# SCH_CameraTrap_2022-12-09.net
KiCad netlist of a schematic drawn in EasyEDA
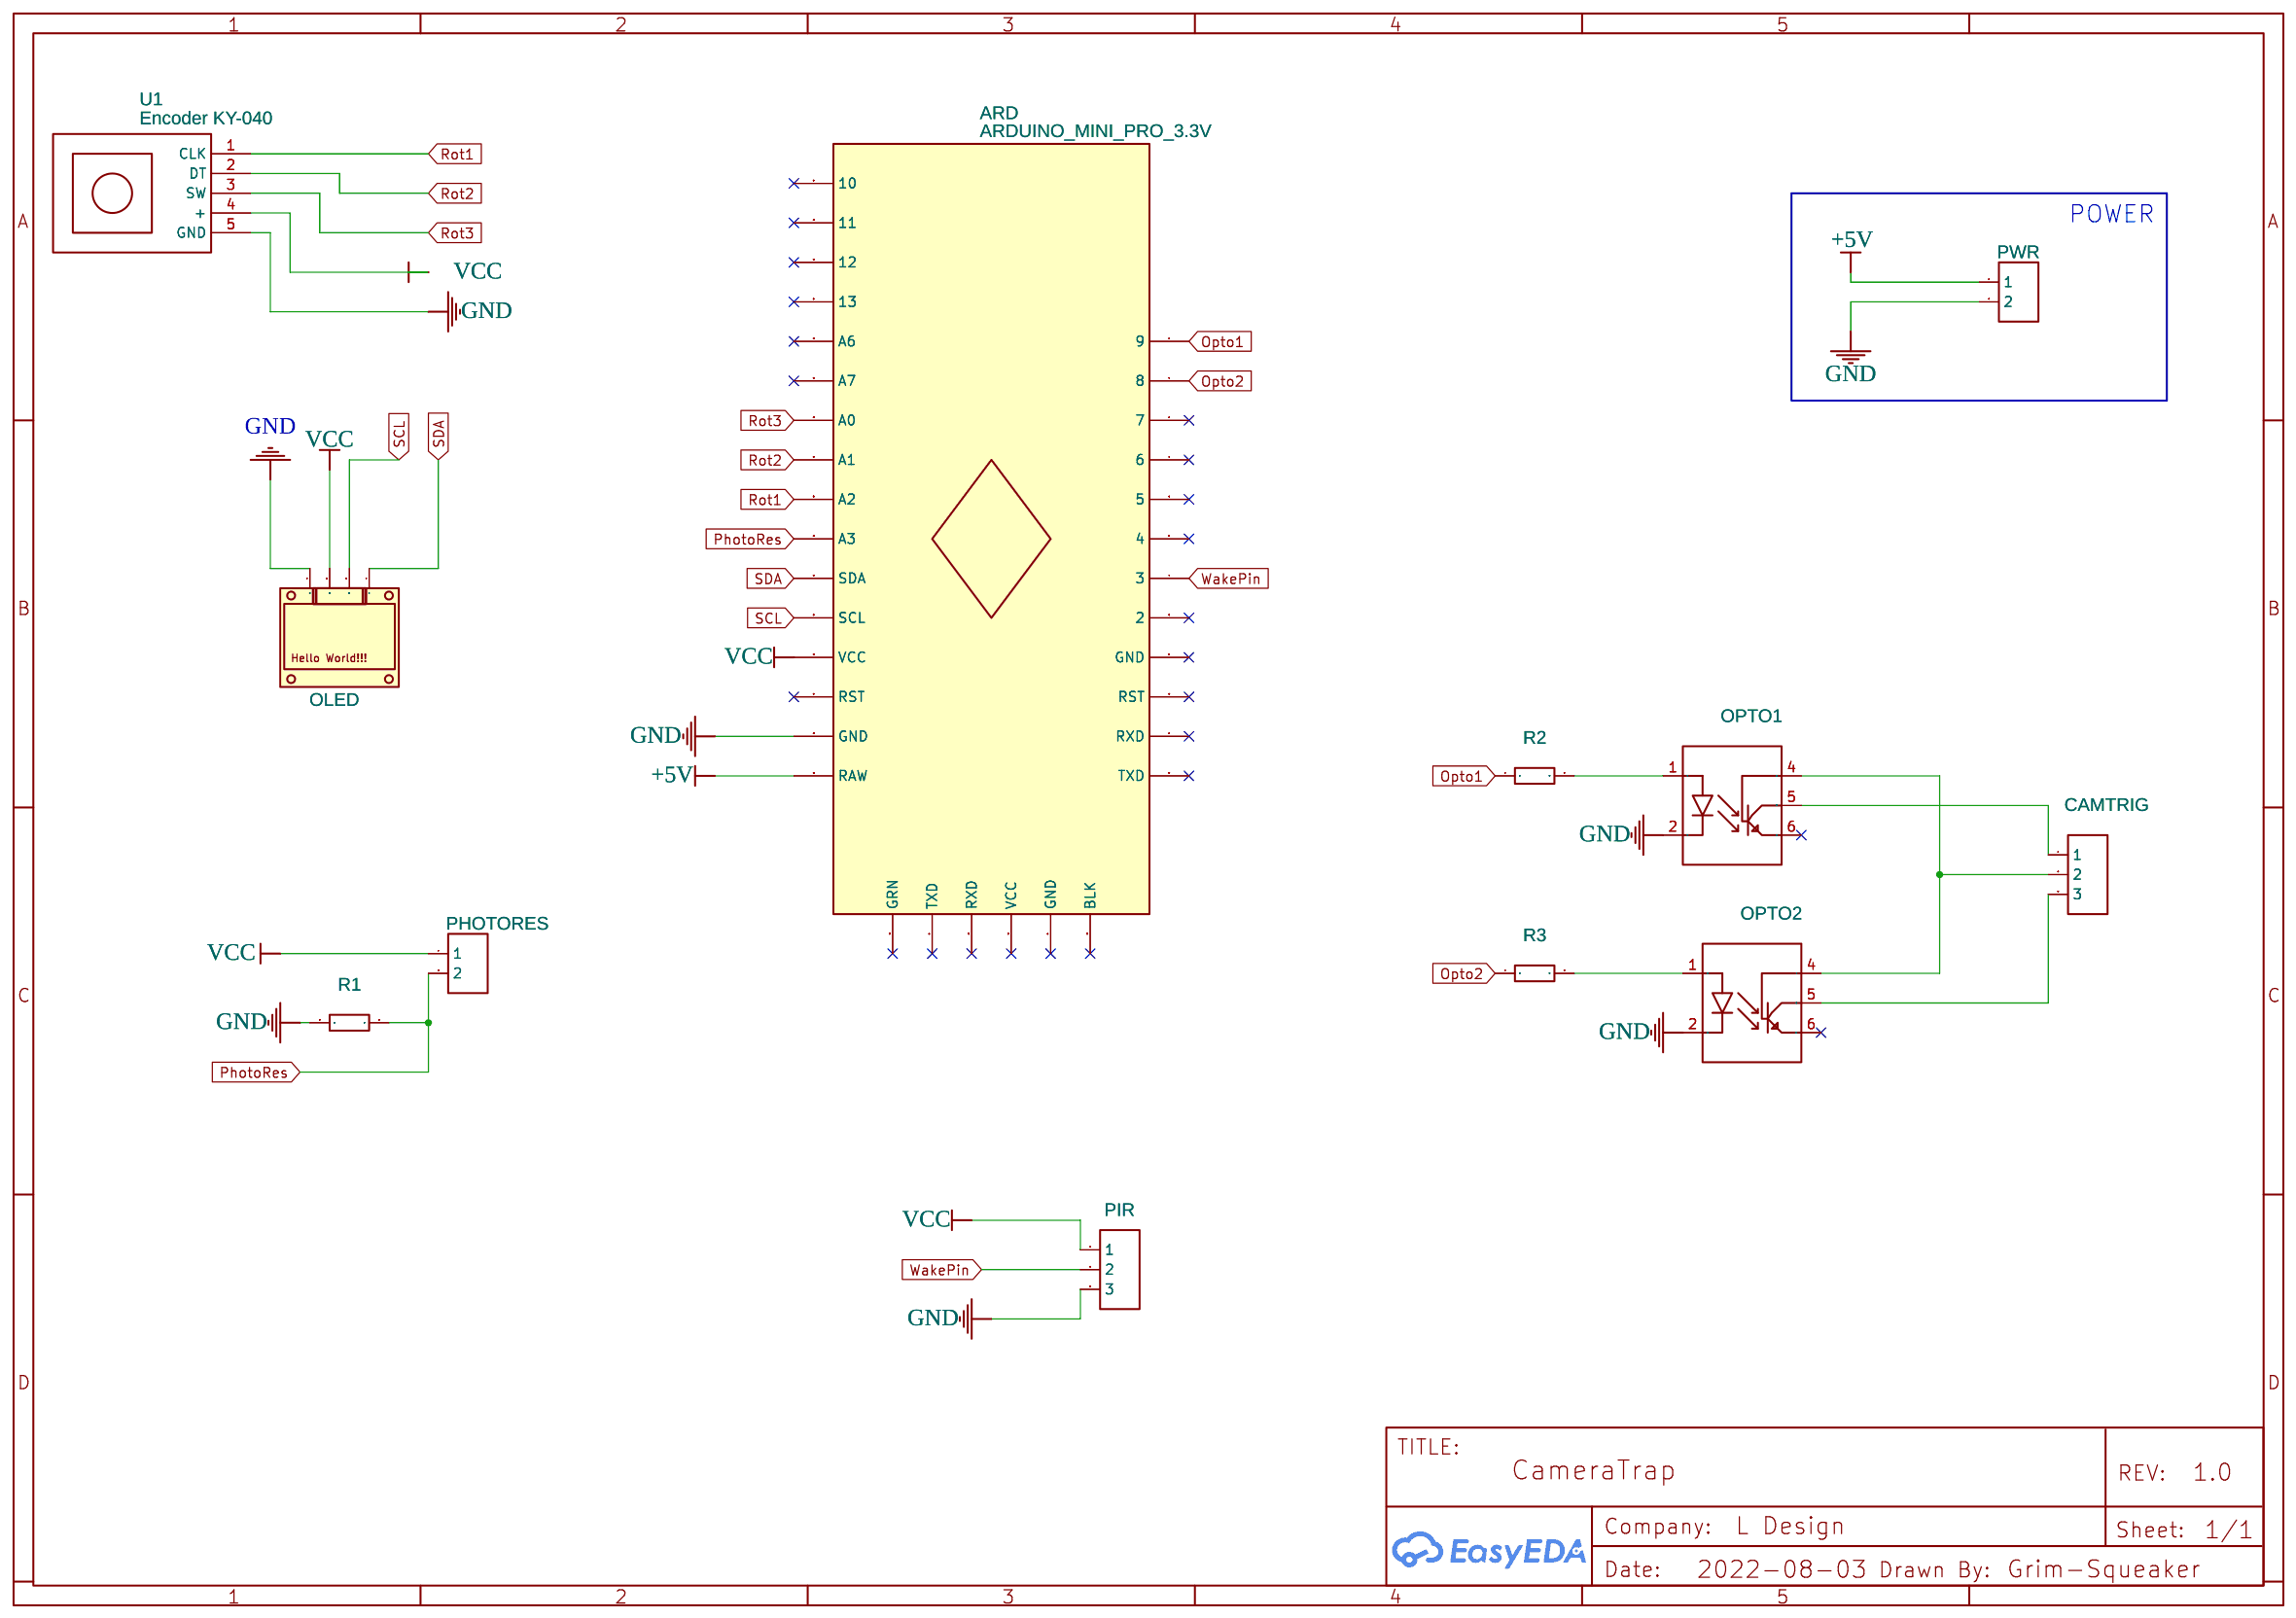
[diagram p0: schematic sheet]

(export (version "E")
  (design (tool "Eeschema 10.0.6"))
  (components
    (comp (ref "ARD")
      (value "ARDUINO_MINI_PRO_3.3V")
      (fields (field (name "BOM_Manufacturer Part") "Spurkfun"))
      (libsource (lib "") (part "ARDUINO_MINI_PRO_3.3V"))
    )
    (comp (ref "CAMTRIG")
      (value "HDR-F-2.54_1x3")
      (fields (field (name "BOM_Supplier Part") "C146690"))
      (libsource (lib "") (part "HDR-F-2.54_1x3_1"))
    )
    (comp (ref "OLED1") (value "OLED") (libsource (lib "") (part "0.96OLED_4P")))
    (comp (ref "OPTO1") (value "CNY-17") (libsource (lib "") (part "CNY-17")))
    (comp (ref "OPTO2") (value "CNY-17") (libsource (lib "") (part "CNY-17")))
    (comp (ref "PHOTORES")
      (value "HDR-F-2.54_1x2")
      (fields (field (name "BOM_Supplier Part") "C49661"))
      (libsource (lib "") (part "HDR-F-2.54_1x2_1"))
    )
    (comp (ref "PIR")
      (value "HDR-F-2.54_1x3")
      (fields (field (name "BOM_Supplier Part") "C146690"))
      (libsource (lib "") (part "HDR-F-2.54_1x3"))
    )
    (comp (ref "PWR")
      (value "HDR-F-2.54_1x2")
      (fields (field (name "BOM_Supplier Part") "C49661"))
      (libsource (lib "") (part "HDR-F-2.54_1x2"))
    )
    (comp (ref "R1")
      (value "10K")
      (fields
        (field (name "BOM_Manufacturer Part") "EWWR0006J10K0T9")
        (field (name "BOM_Supplier Part") "C348946")
      )
      (libsource (lib "") (part "Resistor TH"))
    )
    (comp (ref "R2")
      (value "10K")
      (fields
        (field (name "BOM_Manufacturer Part") "EWWR0006J10K0T9")
        (field (name "BOM_Supplier Part") "C348946")
      )
      (libsource (lib "") (part "Resistor TH"))
    )
    (comp (ref "R3")
      (value "10K")
      (fields
        (field (name "BOM_Manufacturer Part") "EWWR0006J10K0T9")
        (field (name "BOM_Supplier Part") "C348946")
      )
      (libsource (lib "") (part "Resistor TH"))
    )
    (comp (ref "U1") (value "Encoder KY-040") (libsource (lib "") (part "Encoder KY-040")))
  )
  (nets
    (net (code "1") (name "+5V") (class "Default")
      (node (ref "ARD") (pin "19") (pinfunction "RAW_19") (pintype "unspecified"))
      (node (ref "PWR") (pin "1") (pinfunction "1_1") (pintype "input"))
    )
    (net (code "2") (name "GND") (class "Default")
      (node (ref "ARD") (pin "20") (pinfunction "GND_20") (pintype "unspecified"))
      (node (ref "OLED1") (pin "1") (pinfunction "1_1") (pintype "unspecified"))
      (node (ref "OPTO1") (pin "2") (pinfunction "2_2") (pintype "unspecified"))
      (node (ref "OPTO2") (pin "2") (pinfunction "2_2") (pintype "unspecified"))
      (node (ref "PIR") (pin "3") (pinfunction "3_3") (pintype "input"))
      (node (ref "PWR") (pin "2") (pinfunction "2_2") (pintype "input"))
      (node (ref "R1") (pin "1") (pinfunction "1_1") (pintype "unspecified"))
      (node (ref "U1") (pin "5") (pinfunction "GND_5") (pintype "unspecified"))
    )
    (net (code "3") (name "Net-(CAMTRIG-Pad1)") (class "Default")
      (node (ref "CAMTRIG") (pin "1") (pinfunction "1_1") (pintype "input"))
      (node (ref "OPTO1") (pin "5") (pinfunction "5_5") (pintype "unspecified"))
    )
    (net (code "4") (name "Net-(CAMTRIG-Pad2)") (class "Default")
      (node (ref "CAMTRIG") (pin "2") (pinfunction "2_2") (pintype "input"))
      (node (ref "OPTO1") (pin "4") (pinfunction "4_4") (pintype "unspecified"))
      (node (ref "OPTO2") (pin "4") (pinfunction "4_4") (pintype "unspecified"))
    )
    (net (code "5") (name "Net-(CAMTRIG-Pad3)") (class "Default")
      (node (ref "CAMTRIG") (pin "3") (pinfunction "3_3") (pintype "input"))
      (node (ref "OPTO2") (pin "5") (pinfunction "5_5") (pintype "unspecified"))
    )
    (net (code "6") (name "Net-(OPTO1-Pad1)") (class "Default")
      (node (ref "OPTO1") (pin "1") (pinfunction "1_1") (pintype "unspecified"))
      (node (ref "R2") (pin "2") (pinfunction "2_2") (pintype "unspecified"))
    )
    (net (code "7") (name "Net-(OPTO2-Pad1)") (class "Default")
      (node (ref "OPTO2") (pin "1") (pinfunction "1_1") (pintype "unspecified"))
      (node (ref "R3") (pin "2") (pinfunction "2_2") (pintype "unspecified"))
    )
    (net (code "8") (name "Opto1") (class "Default")
      (node (ref "ARD") (pin "1") (pinfunction "9_1") (pintype "unspecified"))
      (node (ref "R2") (pin "1") (pinfunction "1_1") (pintype "unspecified"))
    )
    (net (code "9") (name "Opto2") (class "Default")
      (node (ref "ARD") (pin "2") (pinfunction "8_2") (pintype "unspecified"))
      (node (ref "R3") (pin "1") (pinfunction "1_1") (pintype "unspecified"))
    )
    (net (code "10") (name "PhotoRes") (class "Default")
      (node (ref "ARD") (pin "25") (pinfunction "A3_25") (pintype "unspecified"))
      (node (ref "PHOTORES") (pin "2") (pinfunction "2_2") (pintype "input"))
      (node (ref "R1") (pin "2") (pinfunction "2_2") (pintype "unspecified"))
    )
    (net (code "11") (name "Rot1") (class "Default")
      (node (ref "ARD") (pin "26") (pinfunction "A2_26") (pintype "unspecified"))
      (node (ref "U1") (pin "1") (pinfunction "CLK_1") (pintype "unspecified"))
    )
    (net (code "12") (name "Rot2") (class "Default")
      (node (ref "ARD") (pin "27") (pinfunction "A1_27") (pintype "unspecified"))
      (node (ref "U1") (pin "2") (pinfunction "DT_2") (pintype "unspecified"))
    )
    (net (code "13") (name "Rot3") (class "Default")
      (node (ref "ARD") (pin "28") (pinfunction "A0_28") (pintype "unspecified"))
      (node (ref "U1") (pin "3") (pinfunction "SW_3") (pintype "unspecified"))
    )
    (net (code "14") (name "SCL") (class "Default")
      (node (ref "ARD") (pin "23") (pinfunction "SCL_23") (pintype "unspecified"))
      (node (ref "OLED1") (pin "3") (pinfunction "3_3") (pintype "unspecified"))
    )
    (net (code "15") (name "SDA") (class "Default")
      (node (ref "ARD") (pin "24") (pinfunction "SDA_24") (pintype "unspecified"))
      (node (ref "OLED1") (pin "4") (pinfunction "4_4") (pintype "unspecified"))
    )
    (net (code "16") (name "VCC") (class "Default")
      (node (ref "ARD") (pin "22") (pinfunction "VCC_22") (pintype "unspecified"))
      (node (ref "OLED1") (pin "2") (pinfunction "2_2") (pintype "unspecified"))
      (node (ref "PHOTORES") (pin "1") (pinfunction "1_1") (pintype "input"))
      (node (ref "PIR") (pin "1") (pinfunction "1_1") (pintype "input"))
      (node (ref "U1") (pin "4") (pinfunction "+_4") (pintype "unspecified"))
    )
    (net (code "17") (name "WakePin") (class "Default")
      (node (ref "ARD") (pin "7") (pinfunction "3_7") (pintype "unspecified"))
      (node (ref "PIR") (pin "2") (pinfunction "2_2") (pintype "input"))
    )
    (net (code "18") (name "unconnected-(ARD-2-Pad8)") (class "Default")
      (node (ref "ARD") (pin "8") (pinfunction "2_8") (pintype "unspecified+no_connect"))
    )
    (net (code "19") (name "unconnected-(ARD-4-Pad6)") (class "Default")
      (node (ref "ARD") (pin "6") (pinfunction "4_6") (pintype "unspecified+no_connect"))
    )
    (net (code "20") (name "unconnected-(ARD-6-Pad4)") (class "Default")
      (node (ref "ARD") (pin "4") (pinfunction "6_4") (pintype "unspecified+no_connect"))
    )
    (net (code "21") (name "unconnected-(ARD-7-Pad3)") (class "Default")
      (node (ref "ARD") (pin "3") (pinfunction "7_3") (pintype "unspecified+no_connect"))
    )
    (net (code "22") (name "unconnected-(ARD-10-Pad34)") (class "Default")
      (node (ref "ARD") (pin "34") (pinfunction "10_34") (pintype "unspecified+no_connect"))
    )
    (net (code "23") (name "unconnected-(ARD-11-Pad33)") (class "Default")
      (node (ref "ARD") (pin "33") (pinfunction "11_33") (pintype "unspecified+no_connect"))
    )
    (net (code "24") (name "unconnected-(ARD-12-Pad32)") (class "Default")
      (node (ref "ARD") (pin "32") (pinfunction "12_32") (pintype "unspecified+no_connect"))
    )
    (net (code "25") (name "unconnected-(ARD-13-Pad31)") (class "Default")
      (node (ref "ARD") (pin "31") (pinfunction "13_31") (pintype "unspecified+no_connect"))
    )
    (net (code "26") (name "unconnected-(ARD-A6-Pad30)") (class "Default")
      (node (ref "ARD") (pin "30") (pinfunction "A6_30") (pintype "unspecified+no_connect"))
    )
    (net (code "27") (name "unconnected-(ARD-A7-Pad29)") (class "Default")
      (node (ref "ARD") (pin "29") (pinfunction "A7_29") (pintype "unspecified+no_connect"))
    )
    (net (code "28") (name "unconnected-(ARD-BLK-Pad13)") (class "Default")
      (node (ref "ARD") (pin "13") (pinfunction "BLK_13") (pintype "unspecified+no_connect"))
    )
    (net (code "29") (name "unconnected-(ARD-GND-Pad9)") (class "Default")
      (node (ref "ARD") (pin "9") (pinfunction "GND_9") (pintype "unspecified+no_connect"))
    )
    (net (code "30") (name "unconnected-(ARD-GND-Pad14)") (class "Default")
      (node (ref "ARD") (pin "14") (pinfunction "GND_14") (pintype "unspecified+no_connect"))
    )
    (net (code "31") (name "unconnected-(ARD-GRN-Pad18)") (class "Default")
      (node (ref "ARD") (pin "18") (pinfunction "GRN_18") (pintype "unspecified+no_connect"))
    )
    (net (code "32") (name "unconnected-(ARD-Pad5)") (class "Default")
      (node (ref "ARD") (pin "5") (pinfunction "5_5") (pintype "unspecified+no_connect"))
    )
    (net (code "33") (name "unconnected-(ARD-RST-Pad10)") (class "Default")
      (node (ref "ARD") (pin "10") (pinfunction "RST_10") (pintype "unspecified+no_connect"))
    )
    (net (code "34") (name "unconnected-(ARD-RST-Pad21)") (class "Default")
      (node (ref "ARD") (pin "21") (pinfunction "RST_21") (pintype "unspecified+no_connect"))
    )
    (net (code "35") (name "unconnected-(ARD-RXD-Pad11)") (class "Default")
      (node (ref "ARD") (pin "11") (pinfunction "RXD_11") (pintype "unspecified+no_connect"))
    )
    (net (code "36") (name "unconnected-(ARD-RXD-Pad16)") (class "Default")
      (node (ref "ARD") (pin "16") (pinfunction "RXD_16") (pintype "unspecified+no_connect"))
    )
    (net (code "37") (name "unconnected-(ARD-TXD-Pad12)") (class "Default")
      (node (ref "ARD") (pin "12") (pinfunction "TXD_12") (pintype "unspecified+no_connect"))
    )
    (net (code "38") (name "unconnected-(ARD-TXD-Pad17)") (class "Default")
      (node (ref "ARD") (pin "17") (pinfunction "TXD_17") (pintype "unspecified+no_connect"))
    )
    (net (code "39") (name "unconnected-(ARD-VCC-Pad15)") (class "Default")
      (node (ref "ARD") (pin "15") (pinfunction "VCC_15") (pintype "unspecified+no_connect"))
    )
    (net (code "40") (name "unconnected-(OPTO1-Pad6)") (class "Default")
      (node (ref "OPTO1") (pin "6") (pinfunction "6_6") (pintype "unspecified+no_connect"))
    )
    (net (code "41") (name "unconnected-(OPTO2-Pad6)") (class "Default")
      (node (ref "OPTO2") (pin "6") (pinfunction "6_6") (pintype "unspecified+no_connect"))
    )
  )
)
